# design.net
KiCad netlist of a schematic drawn in EasyEDA Pro
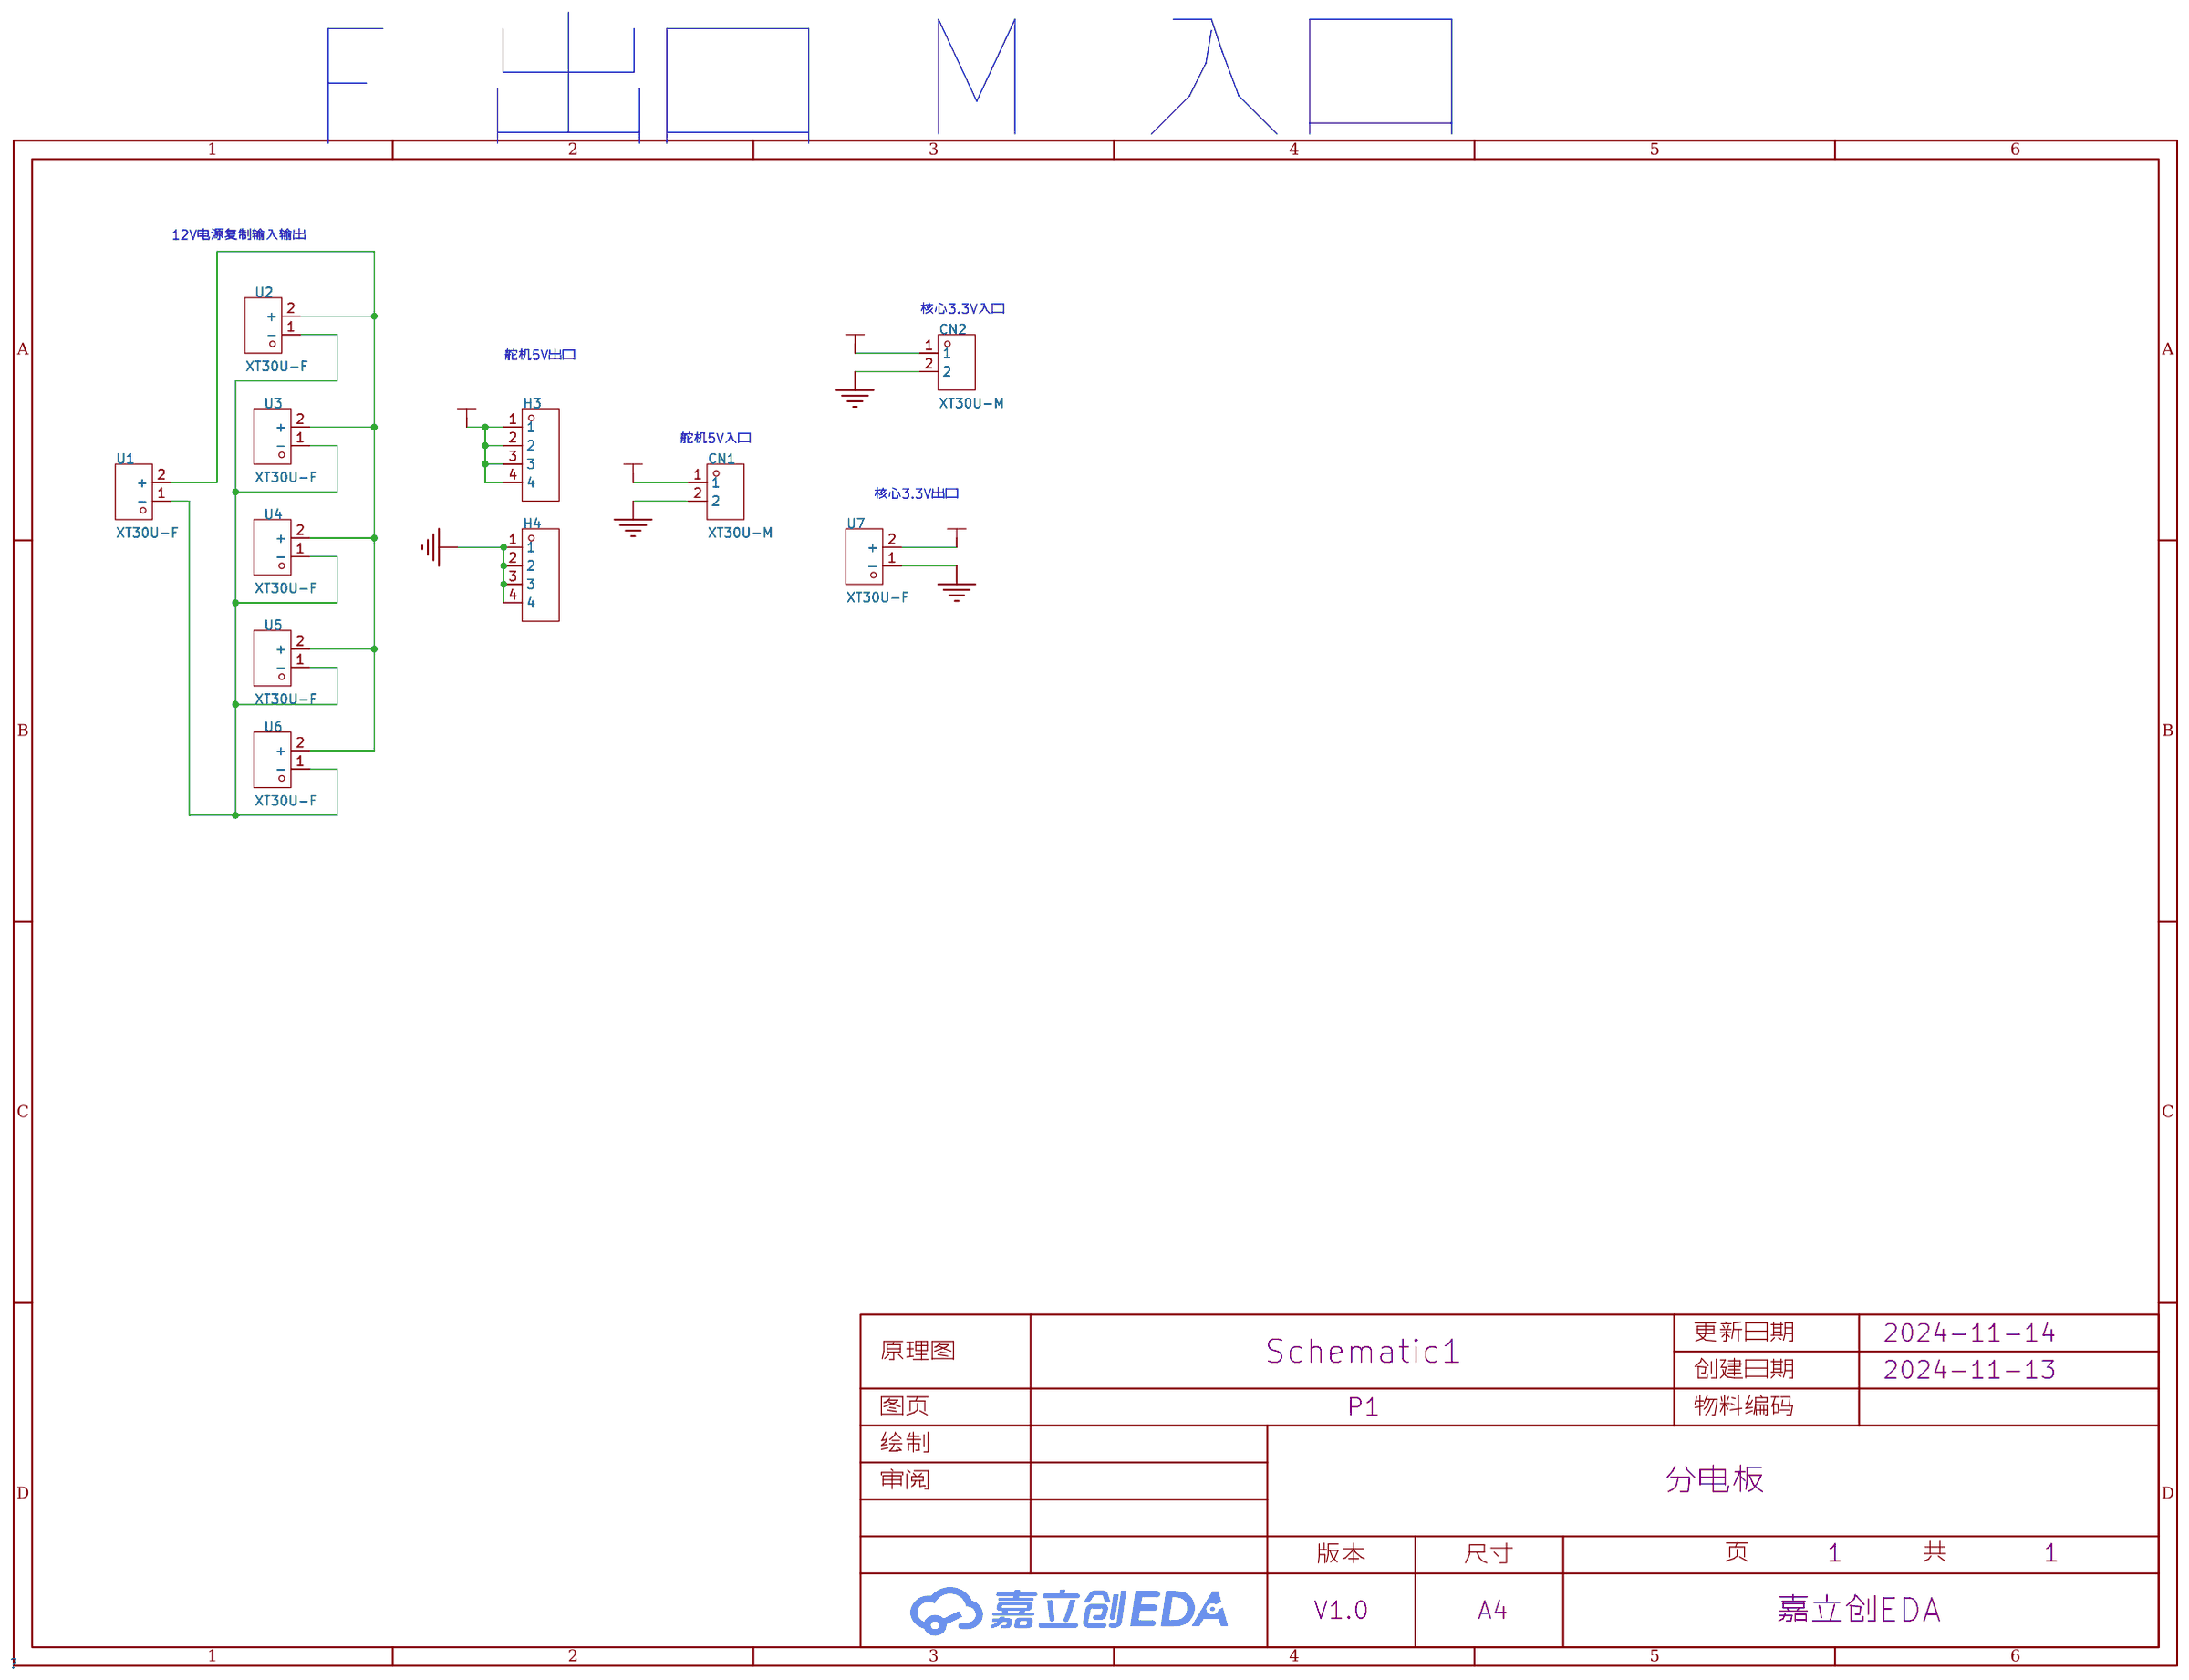
[diagram p0: schematic sheet]

(export (version "E")
  (design (tool "Eeschema 10.0.6"))
  (components
    (comp (ref "CN1")
      (value "XT30U-M")
      (footprint "easyedapro:CONN-TH_XT30U-M")
      (description "类别:-;类型1:-;")
      (fields (field (name "Manufacturer") "AMASS(艾迈斯)"))
      (libsource (lib "easyedapro") (part "XT30U-M"))
    )
    (comp (ref "CN2")
      (value "XT30U-M")
      (footprint "easyedapro:CONN-TH_XT30U-M")
      (description "类别:-;类型1:-;")
      (fields (field (name "Manufacturer") "AMASS(艾迈斯)"))
      (libsource (lib "easyedapro") (part "XT30U-M"))
    )
    (comp (ref "H3")
      (value "~")
      (footprint "easyedapro:HDR-TH_4P-P2.54-V-M")
      (libsource (lib "easyedapro") (part "PZ254V-11-04P"))
    )
    (comp (ref "H4")
      (value "~")
      (footprint "easyedapro:HDR-TH_4P-P2.54-V-M")
      (libsource (lib "easyedapro") (part "PZ254V-11-04P"))
    )
    (comp (ref "U1")
      (value "XT30U-F")
      (footprint "easyedapro:CONN-TH_XT30U-F")
      (description "类别:-;类型1:-;")
      (fields (field (name "Manufacturer") "AMASS(艾迈斯)"))
      (libsource (lib "easyedapro") (part "XT30U-F"))
    )
    (comp (ref "U2")
      (value "XT30U-F")
      (footprint "easyedapro:CONN-TH_XT30U-F")
      (description "类别:-;类型1:-;")
      (fields (field (name "Manufacturer") "AMASS(艾迈斯)"))
      (libsource (lib "easyedapro") (part "XT30U-F"))
    )
    (comp (ref "U3")
      (value "XT30U-F")
      (footprint "easyedapro:CONN-TH_XT30U-F")
      (description "类别:-;类型1:-;")
      (fields (field (name "Manufacturer") "AMASS(艾迈斯)"))
      (libsource (lib "easyedapro") (part "XT30U-F"))
    )
    (comp (ref "U4")
      (value "XT30U-F")
      (footprint "easyedapro:CONN-TH_XT30U-F")
      (description "类别:-;类型1:-;")
      (fields (field (name "Manufacturer") "AMASS(艾迈斯)"))
      (libsource (lib "easyedapro") (part "XT30U-F"))
    )
    (comp (ref "U5")
      (value "XT30U-F")
      (footprint "easyedapro:CONN-TH_XT30U-F")
      (description "类别:-;类型1:-;")
      (fields (field (name "Manufacturer") "AMASS(艾迈斯)"))
      (libsource (lib "easyedapro") (part "XT30U-F"))
    )
    (comp (ref "U6")
      (value "XT30U-F")
      (footprint "easyedapro:CONN-TH_XT30U-F")
      (description "类别:-;类型1:-;")
      (fields (field (name "Manufacturer") "AMASS(艾迈斯)"))
      (libsource (lib "easyedapro") (part "XT30U-F"))
    )
    (comp (ref "U7")
      (value "XT30U-F")
      (footprint "easyedapro:CONN-TH_XT30U-F")
      (description "类别:-;类型1:-;")
      (fields (field (name "Manufacturer") "AMASS(艾迈斯)"))
      (libsource (lib "easyedapro") (part "XT30U-F"))
    )
  )
  (nets
    (net (code "1") (name "3.3V") (class "Default")
      (node (ref "CN2") (pin "1") (pinfunction "1_1") (pintype "unspecified"))
      (node (ref "U7") (pin "2") (pinfunction "+_2") (pintype "unspecified"))
    )
    (net (code "2") (name "5V") (class "Default")
      (node (ref "CN1") (pin "1") (pinfunction "1_1") (pintype "unspecified"))
      (node (ref "H3") (pin "1") (pinfunction "1_1") (pintype "unspecified"))
      (node (ref "H3") (pin "2") (pinfunction "2_2") (pintype "unspecified"))
      (node (ref "H3") (pin "3") (pinfunction "3_3") (pintype "unspecified"))
      (node (ref "H3") (pin "4") (pinfunction "4_4") (pintype "unspecified"))
    )
    (net (code "3") (name "GND") (class "Default")
      (node (ref "CN1") (pin "2") (pinfunction "2_2") (pintype "unspecified"))
      (node (ref "CN2") (pin "2") (pinfunction "2_2") (pintype "unspecified"))
      (node (ref "H4") (pin "1") (pinfunction "1_1") (pintype "unspecified"))
      (node (ref "H4") (pin "2") (pinfunction "2_2") (pintype "unspecified"))
      (node (ref "H4") (pin "3") (pinfunction "3_3") (pintype "unspecified"))
      (node (ref "H4") (pin "4") (pinfunction "4_4") (pintype "unspecified"))
      (node (ref "U7") (pin "1") (pinfunction "-_1") (pintype "unspecified"))
    )
    (net (code "4") (name "Net-(U1-+)") (class "Default")
      (node (ref "U1") (pin "2") (pinfunction "+_2") (pintype "unspecified"))
      (node (ref "U2") (pin "2") (pinfunction "+_2") (pintype "unspecified"))
      (node (ref "U3") (pin "2") (pinfunction "+_2") (pintype "unspecified"))
      (node (ref "U4") (pin "2") (pinfunction "+_2") (pintype "unspecified"))
      (node (ref "U5") (pin "2") (pinfunction "+_2") (pintype "unspecified"))
      (node (ref "U6") (pin "2") (pinfunction "+_2") (pintype "unspecified"))
    )
    (net (code "5") (name "Net-(U1--)") (class "Default")
      (node (ref "U1") (pin "1") (pinfunction "-_1") (pintype "unspecified"))
      (node (ref "U2") (pin "1") (pinfunction "-_1") (pintype "unspecified"))
      (node (ref "U3") (pin "1") (pinfunction "-_1") (pintype "unspecified"))
      (node (ref "U4") (pin "1") (pinfunction "-_1") (pintype "unspecified"))
      (node (ref "U5") (pin "1") (pinfunction "-_1") (pintype "unspecified"))
      (node (ref "U6") (pin "1") (pinfunction "-_1") (pintype "unspecified"))
    )
  )
)
